# config-bank8.net
KiCad netlist of a schematic drawn in Altium Designer
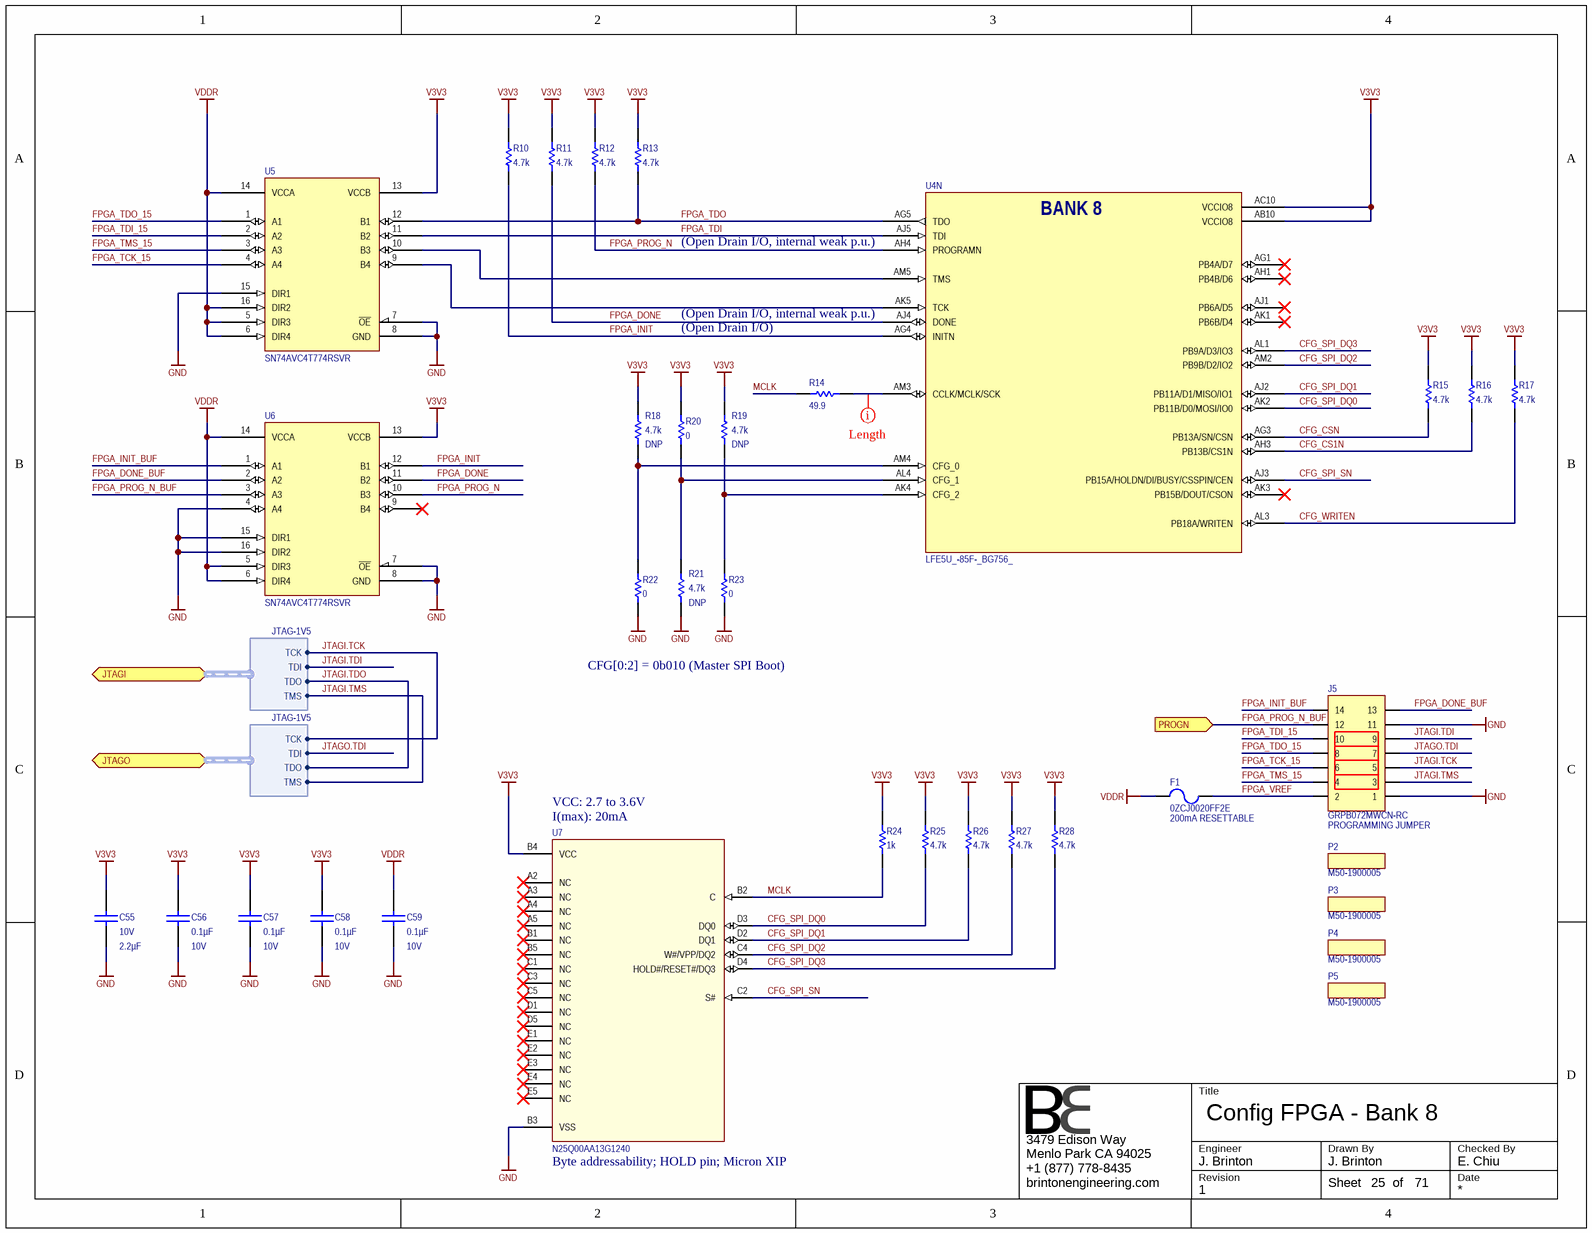
[diagram p0: config-bank8.SchDoc]

(export (version "E")
  (design (tool "Eeschema 10.0.6"))
  (components
    (comp (ref "C55")
      (value "GRM188R71A225KE15D")
      (footprint "CAPC1608X90N")
      (description "CAP CER 2.2UF 10V 10% X7R 0603")
      (fields
        (field (name "MANUFACTURER") "Murata Electronics North America")
        (field (name "TOLERANCE") "±10%")
        (field (name "VOLTAGE - RATED") "10V")
        (field (name "CAPACITANCE") "2.2µF")
      )
      (libsource (lib "murata") (part "GRM188R71A225KE15D"))
    )
    (comp (ref "C56")
      (value "GRM155R71A104KA01J")
      (footprint "CAPC1005X56N")
      (description "CAP CER 0.1UF 10V 10% X7R 0402")
      (fields
        (field (name "MANUFACTURER") "Murata Electronics North America")
        (field (name "TOLERANCE") "±10%")
        (field (name "CAPACITANCE") "0.1µF")
        (field (name "VOLTAGE - RATED") "10V")
      )
      (libsource (lib "murata") (part "GRM155R71A104KA01J"))
    )
    (comp (ref "C57")
      (value "GRM155R71A104KA01J")
      (footprint "CAPC1005X56N")
      (description "CAP CER 0.1UF 10V 10% X7R 0402")
      (fields
        (field (name "MANUFACTURER") "Murata Electronics North America")
        (field (name "TOLERANCE") "±10%")
        (field (name "CAPACITANCE") "0.1µF")
        (field (name "VOLTAGE - RATED") "10V")
      )
      (libsource (lib "murata") (part "GRM155R71A104KA01J"))
    )
    (comp (ref "C58")
      (value "GRM155R71A104KA01J")
      (footprint "CAPC1005X56N")
      (description "CAP CER 0.1UF 10V 10% X7R 0402")
      (fields
        (field (name "MANUFACTURER") "Murata Electronics North America")
        (field (name "TOLERANCE") "±10%")
        (field (name "CAPACITANCE") "0.1µF")
        (field (name "VOLTAGE - RATED") "10V")
      )
      (libsource (lib "murata") (part "GRM155R71A104KA01J"))
    )
    (comp (ref "C59")
      (value "GRM155R71A104KA01J")
      (footprint "CAPC1005X56N")
      (description "CAP CER 0.1UF 10V 10% X7R 0402")
      (fields
        (field (name "MANUFACTURER") "Murata Electronics North America")
        (field (name "TOLERANCE") "±10%")
        (field (name "CAPACITANCE") "0.1µF")
        (field (name "VOLTAGE - RATED") "10V")
      )
      (libsource (lib "murata") (part "GRM155R71A104KA01J"))
    )
    (comp (ref "F1")
      (value "0ZCJ0020FF2E")
      (footprint "generic:1206")
      (description "PTC Resettable Fuse, 0.2A, 30V, SMD 1206")
      (fields (field (name "MANUFACTURER") "Bell Fuse"))
      (libsource (lib "bel-fuse") (part "0ZCJ0020FF2E"))
    )
    (comp (ref "J5")
      (value "GRPB072MWCN-RC")
      (footprint "sullins:GRPB072MWCN-RC")
      (description "Male Header, 0.050\" Pitch, Right Angle, 2x7 Position")
      (fields (field (name "MANUFACTURER") "Sullins"))
      (libsource (lib "sullins") (part "GRPB072MWCN-RC"))
    )
    (comp (ref "P2")
      (value "M50-1900005")
      (description "1.27mm Jumper Socket")
      (fields (field (name "MANUFACTURER") "Harwin"))
      (libsource (lib "harwin") (part "M50-1900005"))
    )
    (comp (ref "P3")
      (value "M50-1900005")
      (description "1.27mm Jumper Socket")
      (fields (field (name "MANUFACTURER") "Harwin"))
      (libsource (lib "harwin") (part "M50-1900005"))
    )
    (comp (ref "P4")
      (value "M50-1900005")
      (description "1.27mm Jumper Socket")
      (fields (field (name "MANUFACTURER") "Harwin"))
      (libsource (lib "harwin") (part "M50-1900005"))
    )
    (comp (ref "P5")
      (value "M50-1900005")
      (description "1.27mm Jumper Socket")
      (fields (field (name "MANUFACTURER") "Harwin"))
      (libsource (lib "harwin") (part "M50-1900005"))
    )
    (comp (ref "R10")
      (value "4.7k")
      (footprint "0603")
      (description "Thick Film Resistor 4.7k Ohms +/-1% 0.1W 75V SMD 0603")
      (fields (field (name "TOLERANCE") "+/-1%") (field (name "MANUFACTURER") "Panasonic - ECG"))
      (libsource (lib "brinton") (part "RES"))
    )
    (comp (ref "R11")
      (value "4.7k")
      (footprint "0603")
      (description "Thick Film Resistor 4.7k Ohms +/-1% 0.1W 75V SMD 0603")
      (fields (field (name "TOLERANCE") "+/-1%") (field (name "MANUFACTURER") "Panasonic - ECG"))
      (libsource (lib "brinton") (part "RES"))
    )
    (comp (ref "R12")
      (value "4.7k")
      (footprint "0603")
      (description "Thick Film Resistor 4.7k Ohms +/-1% 0.1W 75V SMD 0603")
      (fields (field (name "TOLERANCE") "+/-1%") (field (name "MANUFACTURER") "Panasonic - ECG"))
      (libsource (lib "brinton") (part "RES"))
    )
    (comp (ref "R13")
      (value "4.7k")
      (footprint "0603")
      (description "Thick Film Resistor 4.7k Ohms +/-1% 0.1W 75V SMD 0603")
      (fields (field (name "TOLERANCE") "+/-1%") (field (name "MANUFACTURER") "Panasonic - ECG"))
      (libsource (lib "brinton") (part "RES"))
    )
    (comp (ref "R14")
      (value "49.9")
      (footprint "0603")
      (description "Thick Film Resistor 49.9 Ohms +/-1% 0.1W 75V SMD 0603")
      (fields (field (name "TOLERANCE") "+/-1%") (field (name "MANUFACTURER") "Panasonic - ECG"))
      (libsource (lib "brinton") (part "RES"))
    )
    (comp (ref "R15")
      (value "4.7k")
      (footprint "0603")
      (description "Thick Film Resistor 4.7k Ohms +/-1% 0.1W 75V SMD 0603")
      (fields (field (name "TOLERANCE") "+/-1%") (field (name "MANUFACTURER") "Panasonic - ECG"))
      (libsource (lib "brinton") (part "RES"))
    )
    (comp (ref "R16")
      (value "4.7k")
      (footprint "0603")
      (description "Thick Film Resistor 4.7k Ohms +/-1% 0.1W 75V SMD 0603")
      (fields (field (name "TOLERANCE") "+/-1%") (field (name "MANUFACTURER") "Panasonic - ECG"))
      (libsource (lib "brinton") (part "RES"))
    )
    (comp (ref "R17")
      (value "4.7k")
      (footprint "0603")
      (description "Thick Film Resistor 4.7k Ohms +/-1% 0.1W 75V SMD 0603")
      (fields (field (name "TOLERANCE") "+/-1%") (field (name "MANUFACTURER") "Panasonic - ECG"))
      (libsource (lib "brinton") (part "RES"))
    )
    (comp (ref "R18")
      (value "4.7k")
      (footprint "0603")
      (description "Thick Film Resistor 4.7k Ohms +/-1% 0.1W 75V SMD 0603")
      (fields
        (field (name "TOLERANCE") "+/-1%")
        (field (name "MANUFACTURER") "Panasonic - ECG")
        (field (name "DO NOT PLACE") "DNP")
      )
      (libsource (lib "brinton") (part "RES"))
    )
    (comp (ref "R19")
      (value "4.7k")
      (footprint "0603")
      (description "Thick Film Resistor 4.7k Ohms +/-1% 0.1W 75V SMD 0603")
      (fields
        (field (name "TOLERANCE") "+/-1%")
        (field (name "MANUFACTURER") "Panasonic - ECG")
        (field (name "DO NOT PLACE") "DNP")
      )
      (libsource (lib "brinton") (part "RES"))
    )
    (comp (ref "R20")
      (value "0")
      (footprint "0603")
      (description "Thick Film Resistor 0 Ohms SMD 0603")
      (fields (field (name "TOLERANCE") "+/-1%") (field (name "MANUFACTURER") "Panasonic - ECG"))
      (libsource (lib "brinton") (part "RES"))
    )
    (comp (ref "R21")
      (value "4.7k")
      (footprint "0603")
      (description "Thick Film Resistor 4.7k Ohms +/-1% 0.1W 75V SMD 0603")
      (fields
        (field (name "TOLERANCE") "+/-1%")
        (field (name "MANUFACTURER") "Panasonic - ECG")
        (field (name "DO NOT PLACE") "DNP")
      )
      (libsource (lib "brinton") (part "RES"))
    )
    (comp (ref "R22")
      (value "0")
      (footprint "0603")
      (description "Thick Film Resistor 0 Ohms SMD 0603")
      (fields (field (name "TOLERANCE") "+/-1%") (field (name "MANUFACTURER") "Panasonic - ECG"))
      (libsource (lib "brinton") (part "RES"))
    )
    (comp (ref "R23")
      (value "0")
      (footprint "0603")
      (description "Thick Film Resistor 0 Ohms SMD 0603")
      (fields (field (name "TOLERANCE") "+/-1%") (field (name "MANUFACTURER") "Panasonic - ECG"))
      (libsource (lib "brinton") (part "RES"))
    )
    (comp (ref "R24")
      (value "1k")
      (footprint "0603")
      (description "Thick Film Resistor 1k Ohms +/-1% 0.1W 75V SMD 0603")
      (fields (field (name "TOLERANCE") "+/-1%") (field (name "MANUFACTURER") "Panasonic - ECG"))
      (libsource (lib "brinton") (part "RES"))
    )
    (comp (ref "R25")
      (value "4.7k")
      (footprint "0603")
      (description "Thick Film Resistor 4.7k Ohms +/-1% 0.1W 75V SMD 0603")
      (fields (field (name "TOLERANCE") "+/-1%") (field (name "MANUFACTURER") "Panasonic - ECG"))
      (libsource (lib "brinton") (part "RES"))
    )
    (comp (ref "R26")
      (value "4.7k")
      (footprint "0603")
      (description "Thick Film Resistor 4.7k Ohms +/-1% 0.1W 75V SMD 0603")
      (fields (field (name "TOLERANCE") "+/-1%") (field (name "MANUFACTURER") "Panasonic - ECG"))
      (libsource (lib "brinton") (part "RES"))
    )
    (comp (ref "R27")
      (value "4.7k")
      (footprint "0603")
      (description "Thick Film Resistor 4.7k Ohms +/-1% 0.1W 75V SMD 0603")
      (fields (field (name "TOLERANCE") "+/-1%") (field (name "MANUFACTURER") "Panasonic - ECG"))
      (libsource (lib "brinton") (part "RES"))
    )
    (comp (ref "R28")
      (value "4.7k")
      (footprint "0603")
      (description "Thick Film Resistor 4.7k Ohms +/-1% 0.1W 75V SMD 0603")
      (fields (field (name "TOLERANCE") "+/-1%") (field (name "MANUFACTURER") "Panasonic - ECG"))
      (libsource (lib "brinton") (part "RES"))
    )
    (comp (ref "U4")
      (value "LFE5U_-85F-_BG756_")
      (footprint "lattice:caBGA756")
      (description "ECP5 FPGA, 85k LUT, 756-caBGA")
      (fields (field (name "MANUFACTURER") "Lattice Semiconductor"))
      (libsource (lib "lattice") (part "LFE5U_-85F-_BG756_"))
    )
    (comp (ref "U5")
      (value "SN74AVC4T774RSVR")
      (footprint "RSV")
      (description "4-Bit Dual-Supply Bus Transceiver")
      (fields (field (name "MANUFACTURER") "Texas Instruments"))
      (libsource (lib "ti") (part "SN74AVC4T774RSVR"))
    )
    (comp (ref "U6")
      (value "SN74AVC4T774RSVR")
      (footprint "RSV")
      (description "4-Bit Dual-Supply Bus Transceiver")
      (fields (field (name "MANUFACTURER") "Texas Instruments"))
      (libsource (lib "ti") (part "SN74AVC4T774RSVR"))
    )
    (comp (ref "U7")
      (value "N25Q00AA13G1240")
      (footprint "micron:L-PBGA-24")
      (description "1024Mb, 3.3V Serial Flash Memory LBGA24")
      (fields (field (name "MANUFACTURER") "Micron"))
      (libsource (lib "micron") (part "N25Q00AA13G1240"))
    )
  )
  (nets
    (net (code "2") (name "/CFG_CS1N") (class "Default")
      (node (ref "R16") (pin "1") (pinfunction "1_1") (pintype "passive"))
      (node (ref "U4") (pin "AH3") (pinfunction "PB13B/CS1N_AH3") (pintype "bidirectional"))
    )
    (net (code "3") (name "/CFG_CSN") (class "Default")
      (node (ref "R15") (pin "1") (pinfunction "1_1") (pintype "passive"))
      (node (ref "U4") (pin "AG3") (pinfunction "PB13A/SN/CSN_AG3") (pintype "bidirectional"))
    )
    (net (code "4") (name "/CFG_SPI_DQ0") (class "Default")
      (node (ref "R25") (pin "1") (pinfunction "1_1") (pintype "passive"))
      (node (ref "U4") (pin "AK2") (pinfunction "PB11B/D0/MOSI/IO0_AK2") (pintype "bidirectional"))
      (node (ref "U7") (pin "D3") (pinfunction "DQ0_D3") (pintype "bidirectional"))
    )
    (net (code "5") (name "/CFG_SPI_DQ1") (class "Default")
      (node (ref "R26") (pin "1") (pinfunction "1_1") (pintype "passive"))
      (node (ref "U4") (pin "AJ2") (pinfunction "PB11A/D1/MISO/IO1_AJ2") (pintype "bidirectional"))
      (node (ref "U7") (pin "D2") (pinfunction "DQ1_D2") (pintype "bidirectional"))
    )
    (net (code "6") (name "/CFG_SPI_DQ2") (class "Default")
      (node (ref "R27") (pin "1") (pinfunction "1_1") (pintype "passive"))
      (node (ref "U4") (pin "AM2") (pinfunction "PB9B/D2/IO2_AM2") (pintype "bidirectional"))
      (node (ref "U7") (pin "C4") (pinfunction "W#/VPP/DQ2_C4") (pintype "bidirectional"))
    )
    (net (code "7") (name "/CFG_SPI_DQ3") (class "Default")
      (node (ref "R28") (pin "1") (pinfunction "1_1") (pintype "passive"))
      (node (ref "U4") (pin "AL1") (pinfunction "PB9A/D3/IO3_AL1") (pintype "bidirectional"))
      (node (ref "U7") (pin "D4") (pinfunction "HOLD#/RESET#/DQ3_D4") (pintype "bidirectional"))
    )
    (net (code "8") (name "/CFG_SPI_SN") (class "Default")
      (node (ref "U4") (pin "AJ3") (pinfunction "PB15A/HOLDN/DI/BUSY/CSSPIN/CEN_AJ3") (pintype "bidirectional"))
      (node (ref "U7") (pin "C2") (pinfunction "S#_C2") (pintype "input"))
    )
    (net (code "9") (name "/CFG_WRITEN") (class "Default")
      (node (ref "R17") (pin "1") (pinfunction "1_1") (pintype "passive"))
      (node (ref "U4") (pin "AL3") (pinfunction "PB18A/WRITEN_AL3") (pintype "bidirectional"))
    )
    (net (code "10") (name "/FPGA_DONE") (class "Default")
      (node (ref "R11") (pin "1") (pinfunction "1_1") (pintype "passive"))
      (node (ref "U4") (pin "AJ4") (pinfunction "DONE_AJ4") (pintype "bidirectional"))
      (node (ref "U6") (pin "11") (pinfunction "B2_11") (pintype "bidirectional"))
    )
    (net (code "11") (name "/FPGA_DONE_BUF") (class "Default")
      (node (ref "J5") (pin "13") (pinfunction "13_13") (pintype "passive"))
      (node (ref "U6") (pin "2") (pinfunction "A2_2") (pintype "bidirectional"))
    )
    (net (code "12") (name "/FPGA_INIT") (class "Default")
      (node (ref "R10") (pin "1") (pinfunction "1_1") (pintype "passive"))
      (node (ref "U4") (pin "AG4") (pinfunction "INITN_AG4") (pintype "bidirectional"))
      (node (ref "U6") (pin "12") (pinfunction "B1_12") (pintype "bidirectional"))
    )
    (net (code "13") (name "/FPGA_INIT_BUF") (class "Default")
      (node (ref "J5") (pin "14") (pinfunction "14_14") (pintype "passive"))
      (node (ref "U6") (pin "1") (pinfunction "A1_1") (pintype "bidirectional"))
    )
    (net (code "14") (name "/FPGA_PROG_N") (class "Default")
      (node (ref "R12") (pin "1") (pinfunction "1_1") (pintype "passive"))
      (node (ref "U4") (pin "AH4") (pinfunction "PROGRAMN_AH4") (pintype "input"))
      (node (ref "U6") (pin "10") (pinfunction "B3_10") (pintype "bidirectional"))
    )
    (net (code "15") (name "/FPGA_PROG_N_BUF") (class "Default")
      (node (ref "J5") (pin "12") (pinfunction "12_12") (pintype "passive"))
      (node (ref "U6") (pin "3") (pinfunction "A3_3") (pintype "bidirectional"))
    )
    (net (code "16") (name "/FPGA_TCK_15") (class "Default")
      (node (ref "J5") (pin "6") (pinfunction "6_6") (pintype "passive"))
      (node (ref "U5") (pin "4") (pinfunction "A4_4") (pintype "bidirectional"))
    )
    (net (code "17") (name "/FPGA_TDI") (class "Default")
      (node (ref "U4") (pin "AJ5") (pinfunction "TDI_AJ5") (pintype "input"))
      (node (ref "U5") (pin "11") (pinfunction "B2_11") (pintype "bidirectional"))
    )
    (net (code "18") (name "/FPGA_TDI_15") (class "Default")
      (node (ref "J5") (pin "10") (pinfunction "10_10") (pintype "passive"))
      (node (ref "U5") (pin "2") (pinfunction "A2_2") (pintype "bidirectional"))
    )
    (net (code "19") (name "/FPGA_TDO") (class "Default")
      (node (ref "R13") (pin "1") (pinfunction "1_1") (pintype "passive"))
      (node (ref "U4") (pin "AG5") (pinfunction "TDO_AG5") (pintype "output"))
      (node (ref "U5") (pin "12") (pinfunction "B1_12") (pintype "bidirectional"))
    )
    (net (code "20") (name "/FPGA_TDO_15") (class "Default")
      (node (ref "J5") (pin "8") (pinfunction "8_8") (pintype "passive"))
      (node (ref "U5") (pin "1") (pinfunction "A1_1") (pintype "bidirectional"))
    )
    (net (code "21") (name "/FPGA_TMS_15") (class "Default")
      (node (ref "J5") (pin "4") (pinfunction "4_4") (pintype "passive"))
      (node (ref "U5") (pin "3") (pinfunction "A3_3") (pintype "bidirectional"))
    )
    (net (code "22") (name "/FPGA_VREF") (class "Default")
      (node (ref "F1") (pin "2") (pinfunction "2_2") (pintype "passive"))
      (node (ref "J5") (pin "2") (pinfunction "2_2") (pintype "passive"))
    )
    (net (code "23") (name "/JTAGI.TCK") (class "Default")
      (node (ref "J5") (pin "5") (pinfunction "5_5") (pintype "passive"))
    )
    (net (code "24") (name "/JTAGI.TDI") (class "Default")
      (node (ref "J5") (pin "9") (pinfunction "9_9") (pintype "passive"))
    )
    (net (code "26") (name "/JTAGI.TMS") (class "Default")
      (node (ref "J5") (pin "3") (pinfunction "3_3") (pintype "passive"))
    )
    (net (code "27") (name "/JTAGO.TDI") (class "Default")
      (node (ref "J5") (pin "7") (pinfunction "7_7") (pintype "passive"))
    )
    (net (code "28") (name "/MCLK") (class "Default")
      (node (ref "R14") (pin "2") (pinfunction "2_2") (pintype "passive"))
      (node (ref "R24") (pin "1") (pinfunction "1_1") (pintype "passive"))
      (node (ref "U7") (pin "B2") (pinfunction "C_B2") (pintype "input"))
    )
    (net (code "30") (name "GND") (class "Default")
      (node (ref "C55") (pin "1") (pinfunction "1_1") (pintype "passive"))
      (node (ref "C56") (pin "1") (pinfunction "1_1") (pintype "passive"))
      (node (ref "C57") (pin "1") (pinfunction "1_1") (pintype "passive"))
      (node (ref "C58") (pin "1") (pinfunction "1_1") (pintype "passive"))
      (node (ref "C59") (pin "1") (pinfunction "1_1") (pintype "passive"))
      (node (ref "J5") (pin "1") (pinfunction "1_1") (pintype "passive"))
      (node (ref "J5") (pin "11") (pinfunction "11_11") (pintype "passive"))
      (node (ref "R21") (pin "1") (pinfunction "1_1") (pintype "passive"))
      (node (ref "R22") (pin "1") (pinfunction "1_1") (pintype "passive"))
      (node (ref "R23") (pin "1") (pinfunction "1_1") (pintype "passive"))
      (node (ref "U5") (pin "15") (pinfunction "DIR1_15") (pintype "input"))
      (node (ref "U5") (pin "7") (pinfunction "OE_7") (pintype "passive"))
      (node (ref "U5") (pin "8") (pinfunction "GND_8") (pintype "power_in"))
      (node (ref "U6") (pin "15") (pinfunction "DIR1_15") (pintype "input"))
      (node (ref "U6") (pin "16") (pinfunction "DIR2_16") (pintype "input"))
      (node (ref "U6") (pin "4") (pinfunction "A4_4") (pintype "bidirectional"))
      (node (ref "U6") (pin "7") (pinfunction "OE_7") (pintype "passive"))
      (node (ref "U6") (pin "8") (pinfunction "GND_8") (pintype "power_in"))
      (node (ref "U7") (pin "B3") (pinfunction "VSS_B3") (pintype "power_in"))
    )
    (net (code "31") (name "Net-(U4N-CCLK{slash}MCLK{slash}SCK)") (class "Default")
      (node (ref "R14") (pin "1") (pinfunction "1_1") (pintype "passive"))
      (node (ref "U4") (pin "AM3") (pinfunction "CCLK/MCLK/SCK_AM3") (pintype "bidirectional"))
    )
    (net (code "32") (name "Net-(U4N-CFG_0)") (class "Default")
      (node (ref "R18") (pin "1") (pinfunction "1_1") (pintype "passive"))
      (node (ref "R22") (pin "2") (pinfunction "2_2") (pintype "passive"))
      (node (ref "U4") (pin "AM4") (pinfunction "CFG_0_AM4") (pintype "input"))
    )
    (net (code "33") (name "Net-(U4N-CFG_1)") (class "Default")
      (node (ref "R20") (pin "1") (pinfunction "1_1") (pintype "passive"))
      (node (ref "R21") (pin "2") (pinfunction "2_2") (pintype "passive"))
      (node (ref "U4") (pin "AL4") (pinfunction "CFG_1_AL4") (pintype "input"))
    )
    (net (code "34") (name "Net-(U4N-CFG_2)") (class "Default")
      (node (ref "R19") (pin "1") (pinfunction "1_1") (pintype "passive"))
      (node (ref "R23") (pin "2") (pinfunction "2_2") (pintype "passive"))
      (node (ref "U4") (pin "AK4") (pinfunction "CFG_2_AK4") (pintype "input"))
    )
    (net (code "35") (name "Net-(U4N-TCK)") (class "Default")
      (node (ref "U4") (pin "AK5") (pinfunction "TCK_AK5") (pintype "input"))
      (node (ref "U5") (pin "9") (pinfunction "B4_9") (pintype "bidirectional"))
    )
    (net (code "36") (name "Net-(U4N-TMS)") (class "Default")
      (node (ref "U4") (pin "AM5") (pinfunction "TMS_AM5") (pintype "input"))
      (node (ref "U5") (pin "10") (pinfunction "B3_10") (pintype "bidirectional"))
    )
    (net (code "37") (name "V3V3") (class "Default")
      (node (ref "C55") (pin "2") (pinfunction "2_2") (pintype "passive"))
      (node (ref "C56") (pin "2") (pinfunction "2_2") (pintype "passive"))
      (node (ref "C57") (pin "2") (pinfunction "2_2") (pintype "passive"))
      (node (ref "C58") (pin "2") (pinfunction "2_2") (pintype "passive"))
      (node (ref "R10") (pin "2") (pinfunction "2_2") (pintype "passive"))
      (node (ref "R11") (pin "2") (pinfunction "2_2") (pintype "passive"))
      (node (ref "R12") (pin "2") (pinfunction "2_2") (pintype "passive"))
      (node (ref "R13") (pin "2") (pinfunction "2_2") (pintype "passive"))
      (node (ref "R15") (pin "2") (pinfunction "2_2") (pintype "passive"))
      (node (ref "R16") (pin "2") (pinfunction "2_2") (pintype "passive"))
      (node (ref "R17") (pin "2") (pinfunction "2_2") (pintype "passive"))
      (node (ref "R18") (pin "2") (pinfunction "2_2") (pintype "passive"))
      (node (ref "R19") (pin "2") (pinfunction "2_2") (pintype "passive"))
      (node (ref "R20") (pin "2") (pinfunction "2_2") (pintype "passive"))
      (node (ref "R24") (pin "2") (pinfunction "2_2") (pintype "passive"))
      (node (ref "R25") (pin "2") (pinfunction "2_2") (pintype "passive"))
      (node (ref "R26") (pin "2") (pinfunction "2_2") (pintype "passive"))
      (node (ref "R27") (pin "2") (pinfunction "2_2") (pintype "passive"))
      (node (ref "R28") (pin "2") (pinfunction "2_2") (pintype "passive"))
      (node (ref "U4") (pin "AB10") (pinfunction "VCCIO8_AB10") (pintype "power_in"))
      (node (ref "U4") (pin "AC10") (pinfunction "VCCIO8_AC10") (pintype "power_in"))
      (node (ref "U5") (pin "13") (pinfunction "VCCB_13") (pintype "power_in"))
      (node (ref "U6") (pin "13") (pinfunction "VCCB_13") (pintype "power_in"))
      (node (ref "U7") (pin "B4") (pinfunction "VCC_B4") (pintype "power_in"))
    )
    (net (code "38") (name "VDDR") (class "Default")
      (node (ref "C59") (pin "2") (pinfunction "2_2") (pintype "passive"))
      (node (ref "F1") (pin "1") (pinfunction "1_1") (pintype "passive"))
      (node (ref "U5") (pin "14") (pinfunction "VCCA_14") (pintype "power_in"))
      (node (ref "U5") (pin "16") (pinfunction "DIR2_16") (pintype "input"))
      (node (ref "U5") (pin "5") (pinfunction "DIR3_5") (pintype "input"))
      (node (ref "U5") (pin "6") (pinfunction "DIR4_6") (pintype "input"))
      (node (ref "U6") (pin "14") (pinfunction "VCCA_14") (pintype "power_in"))
      (node (ref "U6") (pin "5") (pinfunction "DIR3_5") (pintype "input"))
      (node (ref "U6") (pin "6") (pinfunction "DIR4_6") (pintype "input"))
    )
    (net (code "39") (name "unconnected-(U4N-PB4A{slash}D7-PadAG1)") (class "Default")
      (node (ref "U4") (pin "AG1") (pinfunction "PB4A/D7_AG1") (pintype "bidirectional+no_connect"))
    )
    (net (code "40") (name "unconnected-(U4N-PB4B{slash}D6-PadAH1)") (class "Default")
      (node (ref "U4") (pin "AH1") (pinfunction "PB4B/D6_AH1") (pintype "bidirectional+no_connect"))
    )
    (net (code "41") (name "unconnected-(U4N-PB6A{slash}D5-PadAJ1)") (class "Default")
      (node (ref "U4") (pin "AJ1") (pinfunction "PB6A/D5_AJ1") (pintype "bidirectional+no_connect"))
    )
    (net (code "42") (name "unconnected-(U4N-PB6B{slash}D4-PadAK1)") (class "Default")
      (node (ref "U4") (pin "AK1") (pinfunction "PB6B/D4_AK1") (pintype "bidirectional+no_connect"))
    )
    (net (code "43") (name "unconnected-(U4N-PB15B{slash}DOUT{slash}CSON-PadAK3)") (class "Default")
      (node (ref "U4") (pin "AK3") (pinfunction "PB15B/DOUT/CSON_AK3") (pintype "bidirectional+no_connect"))
    )
    (net (code "44") (name "unconnected-(U6-B4-Pad9)") (class "Default")
      (node (ref "U6") (pin "9") (pinfunction "B4_9") (pintype "bidirectional+no_connect"))
    )
    (net (code "45") (name "unconnected-(U7-NC-PadA2)") (class "Default")
      (node (ref "U7") (pin "A2") (pinfunction "NC_A2") (pintype "passive+no_connect"))
    )
    (net (code "46") (name "unconnected-(U7-NC-PadA3)") (class "Default")
      (node (ref "U7") (pin "A3") (pinfunction "NC_A3") (pintype "passive+no_connect"))
    )
    (net (code "47") (name "unconnected-(U7-NC-PadA4)") (class "Default")
      (node (ref "U7") (pin "A4") (pinfunction "NC_A4") (pintype "passive+no_connect"))
    )
    (net (code "48") (name "unconnected-(U7-NC-PadA5)") (class "Default")
      (node (ref "U7") (pin "A5") (pinfunction "NC_A5") (pintype "passive+no_connect"))
    )
    (net (code "49") (name "unconnected-(U7-NC-PadB1)") (class "Default")
      (node (ref "U7") (pin "B1") (pinfunction "NC_B1") (pintype "passive+no_connect"))
    )
    (net (code "50") (name "unconnected-(U7-NC-PadB5)") (class "Default")
      (node (ref "U7") (pin "B5") (pinfunction "NC_B5") (pintype "passive+no_connect"))
    )
    (net (code "51") (name "unconnected-(U7-NC-PadC1)") (class "Default")
      (node (ref "U7") (pin "C1") (pinfunction "NC_C1") (pintype "passive+no_connect"))
    )
    (net (code "52") (name "unconnected-(U7-NC-PadC3)") (class "Default")
      (node (ref "U7") (pin "C3") (pinfunction "NC_C3") (pintype "passive+no_connect"))
    )
    (net (code "53") (name "unconnected-(U7-NC-PadC5)") (class "Default")
      (node (ref "U7") (pin "C5") (pinfunction "NC_C5") (pintype "passive+no_connect"))
    )
    (net (code "54") (name "unconnected-(U7-NC-PadD1)") (class "Default")
      (node (ref "U7") (pin "D1") (pinfunction "NC_D1") (pintype "passive+no_connect"))
    )
    (net (code "55") (name "unconnected-(U7-NC-PadD5)") (class "Default")
      (node (ref "U7") (pin "D5") (pinfunction "NC_D5") (pintype "passive+no_connect"))
    )
    (net (code "56") (name "unconnected-(U7-NC-PadE1)") (class "Default")
      (node (ref "U7") (pin "E1") (pinfunction "NC_E1") (pintype "passive+no_connect"))
    )
    (net (code "57") (name "unconnected-(U7-NC-PadE2)") (class "Default")
      (node (ref "U7") (pin "E2") (pinfunction "NC_E2") (pintype "passive+no_connect"))
    )
    (net (code "58") (name "unconnected-(U7-NC-PadE3)") (class "Default")
      (node (ref "U7") (pin "E3") (pinfunction "NC_E3") (pintype "passive+no_connect"))
    )
    (net (code "59") (name "unconnected-(U7-NC-PadE4)") (class "Default")
      (node (ref "U7") (pin "E4") (pinfunction "NC_E4") (pintype "passive+no_connect"))
    )
    (net (code "60") (name "unconnected-(U7-NC-PadE5)") (class "Default")
      (node (ref "U7") (pin "E5") (pinfunction "NC_E5") (pintype "passive+no_connect"))
    )
  )
)
